# LM393.net
KiCad netlist of a schematic drawn in EAGLE
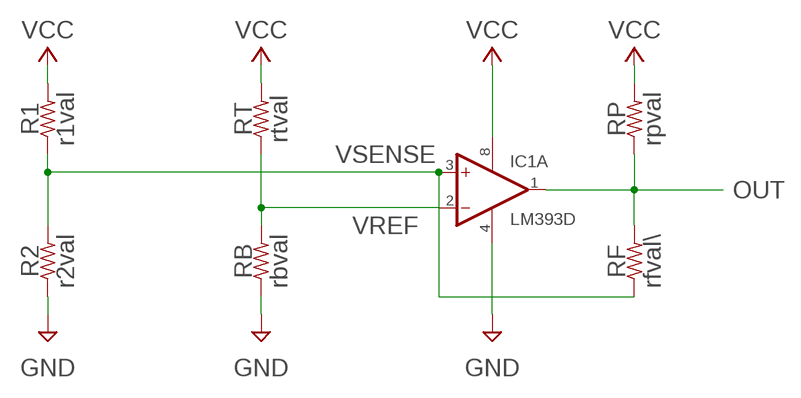
[diagram p0: schematic, sheet 1]

(export (version "E")
  (design (tool "Eeschema 10.0.6"))
  (components
    (comp (ref "IC1")
      (value "LM393D")
      (footprint "eagle-import:SO08")
      (libsource (lib "eagle-import") (part "LM393D"))
    )
    (comp (ref "R1")
      (value "r1val")
      (footprint "eagle-import:0204_7")
      (libsource (lib "eagle-import") (part "R-US_0204/7"))
    )
    (comp (ref "R2")
      (value "r2val")
      (footprint "eagle-import:0204_7")
      (libsource (lib "eagle-import") (part "R-US_0204/7"))
    )
    (comp (ref "RB")
      (value "rbval")
      (footprint "eagle-import:0204_7")
      (libsource (lib "eagle-import") (part "R-US_0204/7"))
    )
    (comp (ref "RF")
      (value "rfval\\")
      (footprint "eagle-import:0204_7")
      (libsource (lib "eagle-import") (part "R-US_0204/7"))
    )
    (comp (ref "RP")
      (value "rpval")
      (footprint "eagle-import:0204_7")
      (libsource (lib "eagle-import") (part "R-US_0204/7"))
    )
    (comp (ref "RT")
      (value "rtval")
      (footprint "eagle-import:0204_7")
      (libsource (lib "eagle-import") (part "R-US_0204/7"))
    )
  )
  (nets
    (net (code "1") (name "/OUT") (class "Default")
      (node (ref "IC1") (pin "1") (pinfunction "OUT_1") (pintype "output"))
      (node (ref "RF") (pin "2") (pinfunction "2_2") (pintype "passive"))
      (node (ref "RP") (pin "1") (pinfunction "1_1") (pintype "passive"))
    )
    (net (code "2") (name "/VREF") (class "Default")
      (node (ref "IC1") (pin "2") (pinfunction "-IN_2") (pintype "input"))
      (node (ref "RB") (pin "2") (pinfunction "2_2") (pintype "passive"))
      (node (ref "RT") (pin "1") (pinfunction "1_1") (pintype "passive"))
    )
    (net (code "3") (name "/VSENSE") (class "Default")
      (node (ref "IC1") (pin "3") (pinfunction "+IN_3") (pintype "input"))
      (node (ref "R1") (pin "1") (pinfunction "1_1") (pintype "passive"))
      (node (ref "R2") (pin "2") (pinfunction "2_2") (pintype "passive"))
      (node (ref "RF") (pin "1") (pinfunction "1_1") (pintype "passive"))
    )
    (net (code "4") (name "GND") (class "Default")
      (node (ref "IC1") (pin "4") (pinfunction "V-_4") (pintype "power_in"))
      (node (ref "R2") (pin "1") (pinfunction "1_1") (pintype "passive"))
      (node (ref "RB") (pin "1") (pinfunction "1_1") (pintype "passive"))
    )
    (net (code "5") (name "VCC") (class "Default")
      (node (ref "IC1") (pin "8") (pinfunction "V+_8") (pintype "power_in"))
      (node (ref "R1") (pin "2") (pinfunction "2_2") (pintype "passive"))
      (node (ref "RP") (pin "2") (pinfunction "2_2") (pintype "passive"))
      (node (ref "RT") (pin "2") (pinfunction "2_2") (pintype "passive"))
    )
  )
)
